# Sensors.net
KiCad netlist of a schematic drawn in Altium Designer
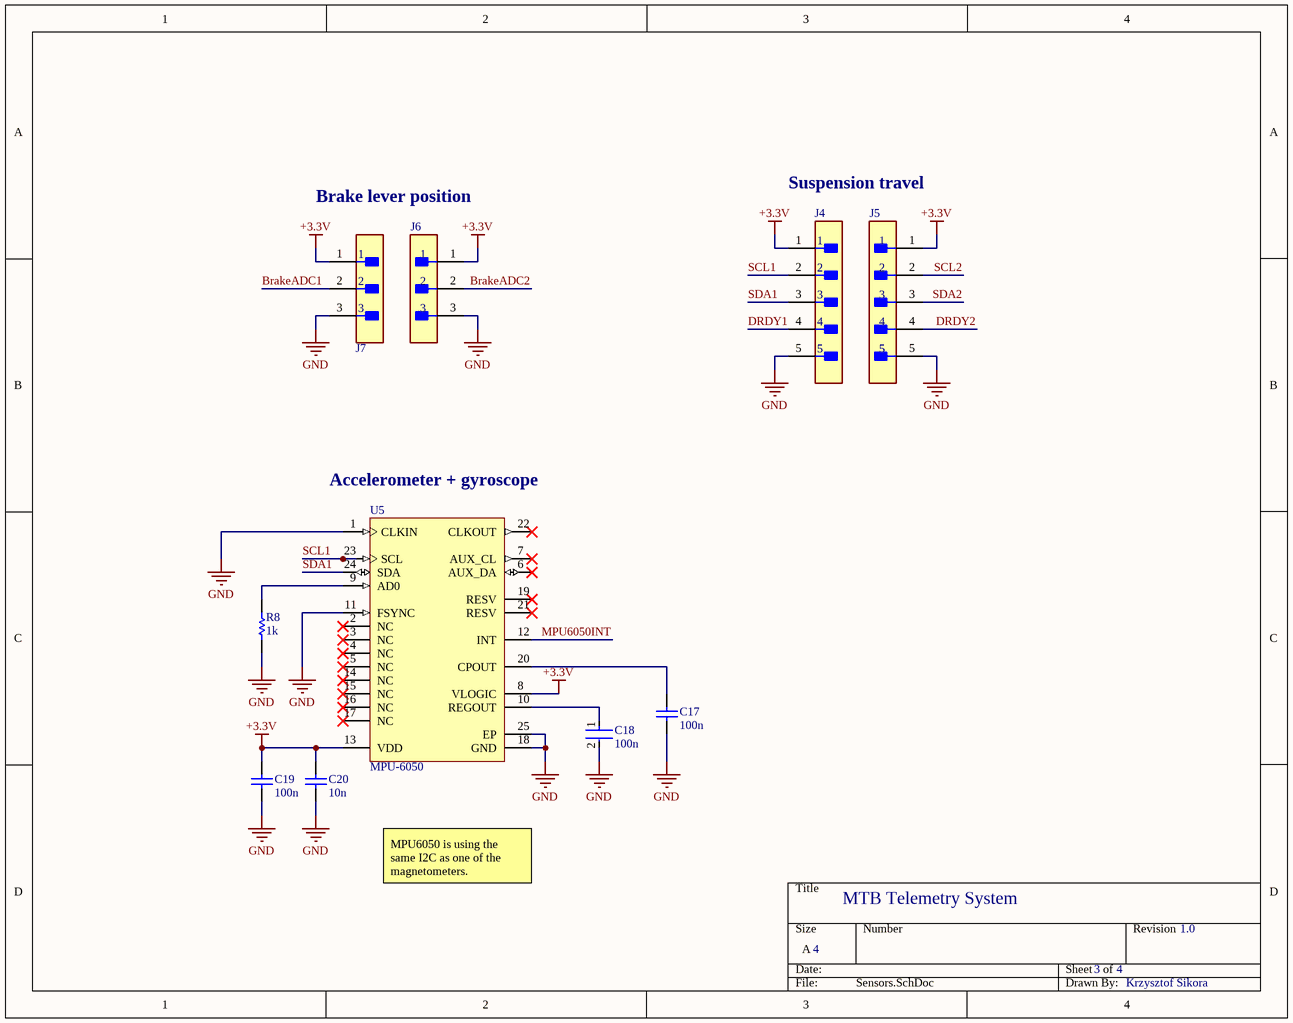
[diagram p0: Sensors.SchDoc]

(export (version "E")
  (design (tool "Eeschema 10.0.6"))
  (components
    (comp (ref "C17")
      (value "100n")
      (footprint "CAPC2013X88X50LL20T25")
      (fields (field (name "MANUFACTURER") "Kemet") (field (name "PART NUMBER") "C0805C103K5RACTU"))
      (libsource (lib "Altium Content Vault") (part "CAP"))
    )
    (comp (ref "C18")
      (value "100n")
      (footprint "FP-C0603C-CF-MFG")
      (description "CAP CER 0.1UF 50V X7R 0603")
      (fields (field (name "TOLERANCE") "0.1") (field (name "MANUFACTURER") "KEMET"))
      (libsource (lib "Altium Content Vault") (part "b4654b650e69147ec39a6b967a45e02"))
    )
    (comp (ref "C19")
      (value "100n")
      (footprint "CAPC2013X88X50LL20T25")
      (fields (field (name "MANUFACTURER") "Kemet") (field (name "PART NUMBER") "C0805C103K5RACTU"))
      (libsource (lib "Altium Content Vault") (part "CAP"))
    )
    (comp (ref "C20")
      (value "10n")
      (footprint "CAPC2013X88X50LL20T25")
      (fields (field (name "MANUFACTURER") "Kemet") (field (name "PART NUMBER") "C0805C103K5RACTU"))
      (libsource (lib "Altium Content Vault") (part "CAP"))
    )
    (comp (ref "J4")
      (value "B5B-XH-AM(LF)(SN)")
      (footprint "FP-B5B-XH-AM_LF_SN-MFG")
      (description "CONN HEADER VERT 5POS 2.5MM")
      (libsource (lib "Altium Content Vault") (part "bf93c07fd2649a848d0ec8585582aab"))
    )
    (comp (ref "J5")
      (value "B5B-XH-AM(LF)(SN)")
      (footprint "FP-B5B-XH-AM_LF_SN-MFG")
      (description "CONN HEADER VERT 5POS 2.5MM")
      (libsource (lib "") (part "bf93c07fd2649a848d0ec8585582aab_1"))
    )
    (comp (ref "J6")
      (value "B3B-XH-A(LF)(SN)")
      (footprint "FP-B3B-XH-A_LF_SN-MFG")
      (description "CONN HEADER VERT 3POS 2.5MM")
      (libsource (lib "Altium Content Vault") (part "0d3f023dd272f625e17a2be33dea85f"))
    )
    (comp (ref "J7")
      (value "B3B-XH-A(LF)(SN)")
      (footprint "FP-B3B-XH-A_LF_SN-MFG")
      (description "CONN HEADER VERT 3POS 2.5MM")
      (libsource (lib "") (part "0d3f023dd272f625e17a2be33dea85f_1"))
    )
    (comp (ref "R8")
      (value "1k")
      (footprint "RESC2013X60X35ML10T20")
      (fields (field (name "TOLERANCE") "5%") (field (name "MANUFACTURER") "Yageo"))
      (libsource (lib "Altium Content Vault") (part "RES-2"))
    )
    (comp (ref "U5")
      (value "MPU-6050")
      (footprint "IS-QFN-24_V")
      (fields (field (name "MANUFACTURER") "InvenSense"))
      (libsource (lib "Altium Content Vault") (part "IS-MPU-6050-QFN-24"))
    )
  )
  (nets
    (net (code "1") (name "+3.3V") (class "Default")
      (node (ref "C19") (pin "2") (pinfunction "2_2") (pintype "passive"))
      (node (ref "C20") (pin "2") (pinfunction "2_2") (pintype "passive"))
      (node (ref "J4") (pin "1") (pinfunction "1_1") (pintype "passive"))
      (node (ref "J5") (pin "1") (pinfunction "1_1") (pintype "passive"))
      (node (ref "J6") (pin "1") (pinfunction "1_1") (pintype "passive"))
      (node (ref "J7") (pin "1") (pinfunction "1_1") (pintype "passive"))
      (node (ref "U5") (pin "13") (pinfunction "VDD_13") (pintype "power_in"))
      (node (ref "U5") (pin "8") (pinfunction "VLOGIC_8") (pintype "power_in"))
    )
    (net (code "2") (name "/BrakeADC1") (class "Default")
      (node (ref "J7") (pin "2") (pinfunction "2_2") (pintype "passive"))
    )
    (net (code "3") (name "/BrakeADC2") (class "Default")
      (node (ref "J6") (pin "2") (pinfunction "2_2") (pintype "passive"))
    )
    (net (code "4") (name "/DRDY1") (class "Default")
      (node (ref "J4") (pin "4") (pinfunction "4_4") (pintype "passive"))
    )
    (net (code "5") (name "/DRDY2") (class "Default")
      (node (ref "J5") (pin "4") (pinfunction "4_4") (pintype "passive"))
    )
    (net (code "6") (name "/MPU6050INT") (class "Default")
      (node (ref "U5") (pin "12") (pinfunction "INT_12") (pintype "open_collector"))
    )
    (net (code "7") (name "/SCL1") (class "Default")
      (node (ref "J4") (pin "2") (pinfunction "2_2") (pintype "passive"))
      (node (ref "U5") (pin "23") (pinfunction "SCL_23") (pintype "input"))
    )
    (net (code "8") (name "/SCL2") (class "Default")
      (node (ref "J5") (pin "2") (pinfunction "2_2") (pintype "passive"))
    )
    (net (code "9") (name "/SDA1") (class "Default")
      (node (ref "J4") (pin "3") (pinfunction "3_3") (pintype "passive"))
      (node (ref "U5") (pin "24") (pinfunction "SDA_24") (pintype "bidirectional"))
    )
    (net (code "10") (name "/SDA2") (class "Default")
      (node (ref "J5") (pin "3") (pinfunction "3_3") (pintype "passive"))
    )
    (net (code "11") (name "GND") (class "Default")
      (node (ref "C17") (pin "1") (pinfunction "1_1") (pintype "passive"))
      (node (ref "C18") (pin "2") (pinfunction "2_2") (pintype "passive"))
      (node (ref "C19") (pin "1") (pinfunction "1_1") (pintype "passive"))
      (node (ref "C20") (pin "1") (pinfunction "1_1") (pintype "passive"))
      (node (ref "J4") (pin "5") (pinfunction "5_5") (pintype "passive"))
      (node (ref "J5") (pin "5") (pinfunction "5_5") (pintype "passive"))
      (node (ref "J6") (pin "3") (pinfunction "3_3") (pintype "passive"))
      (node (ref "J7") (pin "3") (pinfunction "3_3") (pintype "passive"))
      (node (ref "R8") (pin "1") (pinfunction "1_1") (pintype "passive"))
      (node (ref "U5") (pin "1") (pinfunction "CLKIN_1") (pintype "input"))
      (node (ref "U5") (pin "11") (pinfunction "FSYNC_11") (pintype "input"))
      (node (ref "U5") (pin "18") (pinfunction "GND_18") (pintype "power_in"))
      (node (ref "U5") (pin "25") (pinfunction "EP_25") (pintype "power_in"))
    )
    (net (code "12") (name "Net-(U5-AD0)") (class "Default")
      (node (ref "R8") (pin "2") (pinfunction "2_2") (pintype "passive"))
      (node (ref "U5") (pin "9") (pinfunction "AD0_9") (pintype "input"))
    )
    (net (code "13") (name "Net-(U5-CPOUT)") (class "Default")
      (node (ref "C17") (pin "2") (pinfunction "2_2") (pintype "passive"))
      (node (ref "U5") (pin "20") (pinfunction "CPOUT_20") (pintype "passive"))
    )
    (net (code "14") (name "Net-(U5-REGOUT)") (class "Default")
      (node (ref "C18") (pin "1") (pinfunction "1_1") (pintype "passive"))
      (node (ref "U5") (pin "10") (pinfunction "REGOUT_10") (pintype "passive"))
    )
    (net (code "15") (name "unconnected-(U5-AUX_CL-Pad7)") (class "Default")
      (node (ref "U5") (pin "7") (pinfunction "AUX_CL_7") (pintype "output+no_connect"))
    )
    (net (code "16") (name "unconnected-(U5-AUX_DA-Pad6)") (class "Default")
      (node (ref "U5") (pin "6") (pinfunction "AUX_DA_6") (pintype "bidirectional+no_connect"))
    )
    (net (code "17") (name "unconnected-(U5-CLKOUT-Pad22)") (class "Default")
      (node (ref "U5") (pin "22") (pinfunction "CLKOUT_22") (pintype "output+no_connect"))
    )
    (net (code "18") (name "unconnected-(U5-NC-Pad2)") (class "Default")
      (node (ref "U5") (pin "2") (pinfunction "NC_2") (pintype "passive+no_connect"))
    )
    (net (code "19") (name "unconnected-(U5-NC-Pad3)") (class "Default")
      (node (ref "U5") (pin "3") (pinfunction "NC_3") (pintype "passive+no_connect"))
    )
    (net (code "20") (name "unconnected-(U5-NC-Pad4)") (class "Default")
      (node (ref "U5") (pin "4") (pinfunction "NC_4") (pintype "passive+no_connect"))
    )
    (net (code "21") (name "unconnected-(U5-NC-Pad5)") (class "Default")
      (node (ref "U5") (pin "5") (pinfunction "NC_5") (pintype "passive+no_connect"))
    )
    (net (code "22") (name "unconnected-(U5-NC-Pad14)") (class "Default")
      (node (ref "U5") (pin "14") (pinfunction "NC_14") (pintype "passive+no_connect"))
    )
    (net (code "23") (name "unconnected-(U5-NC-Pad15)") (class "Default")
      (node (ref "U5") (pin "15") (pinfunction "NC_15") (pintype "passive+no_connect"))
    )
    (net (code "24") (name "unconnected-(U5-NC-Pad16)") (class "Default")
      (node (ref "U5") (pin "16") (pinfunction "NC_16") (pintype "passive+no_connect"))
    )
    (net (code "25") (name "unconnected-(U5-NC-Pad17)") (class "Default")
      (node (ref "U5") (pin "17") (pinfunction "NC_17") (pintype "passive+no_connect"))
    )
    (net (code "26") (name "unconnected-(U5-RESV-Pad19)") (class "Default")
      (node (ref "U5") (pin "19") (pinfunction "RESV_19") (pintype "passive+no_connect"))
    )
    (net (code "27") (name "unconnected-(U5-RESV-Pad21)") (class "Default")
      (node (ref "U5") (pin "21") (pinfunction "RESV_21") (pintype "passive+no_connect"))
    )
  )
)
